# Tritag_Color_Sensor_Board_1_1.net
KiCad netlist of a schematic drawn in EAGLE
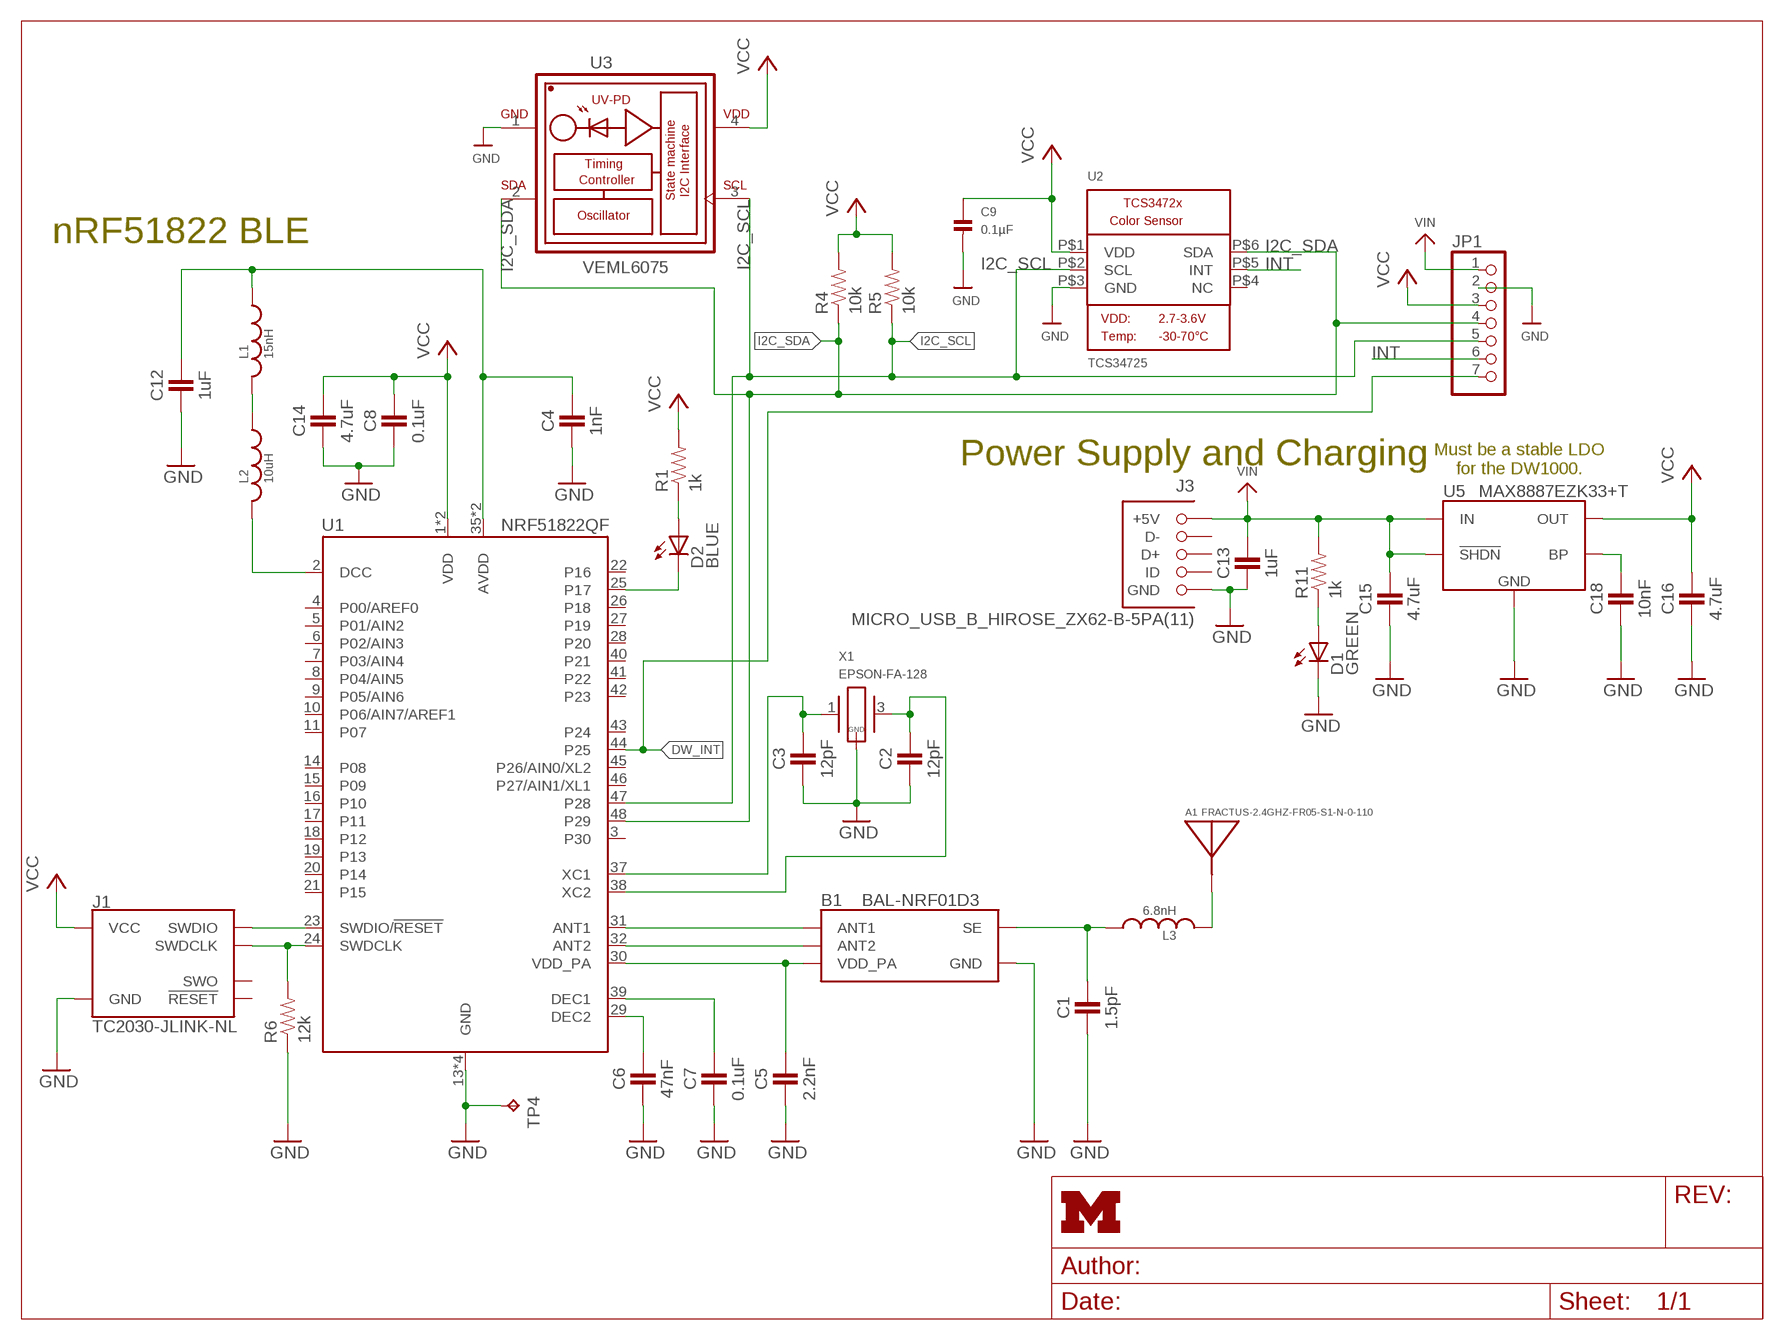
[diagram p0: schematic, sheet 1]

(export (version "E")
  (design (tool "Eeschema 10.0.6"))
  (components
    (comp (ref "A1")
      (value "FRACTUS-2.4GHZ-FR05-S1-N-0-110")
      (footprint "eagle-import:FRACTUS-ANTENNA-FR05-S1-N-0-110")
      (libsource (lib "eagle-import") (part "FRACTUS-2.4GHZ-FR05-S1-N-0-110"))
    )
    (comp (ref "B1")
      (value "BAL-NRF01D3")
      (footprint "eagle-import:BAL-NRF01D3")
      (libsource (lib "eagle-import") (part "BAL-NRF01D3"))
    )
    (comp (ref "C1")
      (value "1.5pF")
      (footprint "eagle-import:0402_CAP")
      (libsource (lib "eagle-import") (part "CAPACITOR"))
    )
    (comp (ref "C2")
      (value "12pF")
      (footprint "eagle-import:0402_CAP")
      (libsource (lib "eagle-import") (part "CAPACITOR"))
    )
    (comp (ref "C3")
      (value "12pF")
      (footprint "eagle-import:0402_CAP")
      (libsource (lib "eagle-import") (part "CAPACITOR"))
    )
    (comp (ref "C4")
      (value "1nF")
      (footprint "eagle-import:0402_CAP")
      (libsource (lib "eagle-import") (part "CAPACITOR"))
    )
    (comp (ref "C5")
      (value "2.2nF")
      (footprint "eagle-import:0402_CAP")
      (libsource (lib "eagle-import") (part "CAPACITOR"))
    )
    (comp (ref "C6")
      (value "47nF")
      (footprint "eagle-import:0402_CAP")
      (libsource (lib "eagle-import") (part "CAPACITOR"))
    )
    (comp (ref "C7")
      (value "0.1uF")
      (footprint "eagle-import:0402_CAP")
      (libsource (lib "eagle-import") (part "CAPACITOR"))
    )
    (comp (ref "C8")
      (value "0.1uF")
      (footprint "eagle-import:0402_CAP")
      (libsource (lib "eagle-import") (part "CAPACITOR"))
    )
    (comp (ref "C9")
      (value "0.1µF")
      (footprint "eagle-import:_0805")
      (libsource (lib "eagle-import") (part "CAP_CERAMIC_0805"))
    )
    (comp (ref "C12")
      (value "1uF")
      (footprint "eagle-import:0402_CAP")
      (libsource (lib "eagle-import") (part "CAPACITOR"))
    )
    (comp (ref "C13")
      (value "1uF")
      (footprint "eagle-import:0402_CAP")
      (libsource (lib "eagle-import") (part "CAPACITOR"))
    )
    (comp (ref "C14")
      (value "4.7uF")
      (footprint "eagle-import:0402_CAP")
      (libsource (lib "eagle-import") (part "CAPACITOR"))
    )
    (comp (ref "C15")
      (value "4.7uF")
      (footprint "eagle-import:0402_CAP")
      (libsource (lib "eagle-import") (part "CAPACITOR"))
    )
    (comp (ref "C16")
      (value "4.7uF")
      (footprint "eagle-import:0402_CAP")
      (libsource (lib "eagle-import") (part "CAPACITOR"))
    )
    (comp (ref "C18")
      (value "10nF")
      (footprint "eagle-import:0402_CAP")
      (libsource (lib "eagle-import") (part "CAPACITOR"))
    )
    (comp (ref "D1")
      (value "GREEN")
      (footprint "eagle-import:LED-0603")
      (libsource (lib "eagle-import") (part "LED0603"))
    )
    (comp (ref "D2")
      (value "BLUE")
      (footprint "eagle-import:LED-0603")
      (libsource (lib "eagle-import") (part "LED0603"))
    )
    (comp (ref "J1")
      (value "TC2030-JLINK-NL")
      (footprint "eagle-import:TC2030-IDC-NL")
      (libsource (lib "eagle-import") (part "TC2030-JLINK-NL"))
    )
    (comp (ref "J3")
      (value "MICRO_USB_B_HIROSE_ZX62-B-5PA(11)")
      (footprint "eagle-import:USB_MICRO_B-HIROSE-ZX62-B-5PA(11)")
      (libsource (lib "eagle-import") (part "MICRO_USB_B_HIROSE_ZX62-B-5PA(11)"))
    )
    (comp (ref "JP1")
      (value "HEADER-1X770MIL")
      (footprint "eagle-import:1X07_ROUND_70")
      (libsource (lib "eagle-import") (part "HEADER-1X770MIL"))
    )
    (comp (ref "L1")
      (value "15nH")
      (footprint "eagle-import:0402_CAP")
      (libsource (lib "eagle-import") (part "INDUCTOR0402"))
    )
    (comp (ref "L2")
      (value "10uH")
      (footprint "eagle-import:0603_CAP")
      (libsource (lib "eagle-import") (part "INDUCTOR0603"))
    )
    (comp (ref "L3")
      (value "6.8nH")
      (footprint "eagle-import:0402_CAP")
      (libsource (lib "eagle-import") (part "INDUCTOR0402"))
    )
    (comp (ref "R1")
      (value "1k")
      (footprint "eagle-import:0402_RES")
      (libsource (lib "eagle-import") (part "RESISTOR0402_RES"))
    )
    (comp (ref "R4")
      (value "10k")
      (footprint "eagle-import:0402_RES")
      (libsource (lib "eagle-import") (part "RESISTOR0402_RES"))
    )
    (comp (ref "R5")
      (value "10k")
      (footprint "eagle-import:0402_RES")
      (libsource (lib "eagle-import") (part "RESISTOR0402_RES"))
    )
    (comp (ref "R6")
      (value "12k")
      (footprint "eagle-import:0402_RES")
      (libsource (lib "eagle-import") (part "RESISTOR0402_RES"))
    )
    (comp (ref "R11")
      (value "1k")
      (footprint "eagle-import:0402_RES")
      (libsource (lib "eagle-import") (part "RESISTOR0402_RES"))
    )
    (comp (ref "TP4")
      (value "TPTP06SQ")
      (footprint "eagle-import:TP06SQ")
      (libsource (lib "eagle-import") (part "TPTP06SQ"))
    )
    (comp (ref "U1")
      (value "NRF51822QF")
      (footprint "eagle-import:QFN-48-6MM")
      (libsource (lib "eagle-import") (part "NRF51822QF"))
    )
    (comp (ref "U2")
      (value "TCS34725")
      (footprint "eagle-import:TCS3472_FN6")
      (libsource (lib "eagle-import") (part "LIGHT_TCS3472"))
    )
    (comp (ref "U3")
      (value "VEML6075")
      (footprint "eagle-import:VISHAY_VEML6075_1.25X2X1")
      (fields
        (field (name "DIGI-KEY_PART_NUMBER") "VEML6075CT-ND")
        (field (name "MF") "Vishay Semiconductor")
      )
      (libsource (lib "eagle-import") (part "VEML6075"))
    )
    (comp (ref "U5")
      (value "MAX8887EZK33+T")
      (footprint "eagle-import:SOT-23-5")
      (libsource (lib "eagle-import") (part "MAX8887EZK33+T"))
    )
    (comp (ref "X1")
      (value "EPSON-FA-128")
      (footprint "eagle-import:FA-128")
      (libsource (lib "eagle-import") (part "EPSON-FA-128"))
    )
  )
  (nets
    (net (code "1") (name "/INT") (class "Default")
      (node (ref "JP1") (pin "6") (pinfunction "6_6") (pintype "passive"))
      (node (ref "U2") (pin "P$5") (pinfunction "INT_P$5") (pintype "output"))
    )
    (net (code "2") (name "DW_INT") (class "Default")
      (node (ref "JP1") (pin "7") (pinfunction "7_7") (pintype "passive"))
      (node (ref "U1") (pin "44") (pinfunction "P25_44") (pintype "bidirectional"))
    )
    (net (code "3") (name "GND") (class "Default")
      (node (ref "B1") (pin "GND") (pinfunction "GND_GND") (pintype "bidirectional"))
      (node (ref "C1") (pin "2") (pinfunction "2_2") (pintype "bidirectional"))
      (node (ref "C12") (pin "2") (pinfunction "2_2") (pintype "bidirectional"))
      (node (ref "C13") (pin "2") (pinfunction "2_2") (pintype "bidirectional"))
      (node (ref "C14") (pin "2") (pinfunction "2_2") (pintype "bidirectional"))
      (node (ref "C15") (pin "2") (pinfunction "2_2") (pintype "bidirectional"))
      (node (ref "C16") (pin "2") (pinfunction "2_2") (pintype "bidirectional"))
      (node (ref "C18") (pin "2") (pinfunction "2_2") (pintype "bidirectional"))
      (node (ref "C2") (pin "2") (pinfunction "2_2") (pintype "bidirectional"))
      (node (ref "C3") (pin "2") (pinfunction "2_2") (pintype "bidirectional"))
      (node (ref "C4") (pin "2") (pinfunction "2_2") (pintype "bidirectional"))
      (node (ref "C5") (pin "2") (pinfunction "2_2") (pintype "bidirectional"))
      (node (ref "C6") (pin "2") (pinfunction "2_2") (pintype "bidirectional"))
      (node (ref "C7") (pin "2") (pinfunction "2_2") (pintype "bidirectional"))
      (node (ref "C8") (pin "2") (pinfunction "2_2") (pintype "bidirectional"))
      (node (ref "C9") (pin "2") (pinfunction "P$2_2") (pintype "passive"))
      (node (ref "D1") (pin "C") (pinfunction "C_C") (pintype "passive"))
      (node (ref "J1") (pin "5") (pinfunction "GND_5") (pintype "bidirectional"))
      (node (ref "J3") (pin "5") (pinfunction "GND_5") (pintype "bidirectional"))
      (node (ref "JP1") (pin "2") (pinfunction "2_2") (pintype "passive"))
      (node (ref "R6") (pin "1") (pinfunction "1_1") (pintype "passive"))
      (node (ref "TP4") (pin "TP") (pinfunction "TP_TP") (pintype "input"))
      (node (ref "U1") (pin "13") (pinfunction "GND_13") (pintype "bidirectional"))
      (node (ref "U1") (pin "33") (pinfunction "GND_33") (pintype "bidirectional"))
      (node (ref "U1") (pin "34") (pinfunction "GND_34") (pintype "bidirectional"))
      (node (ref "U1") (pin "GND") (pinfunction "GND_GND") (pintype "bidirectional"))
      (node (ref "U2") (pin "P$3") (pinfunction "GND_P$3") (pintype "power_in"))
      (node (ref "U3") (pin "1") (pinfunction "GND_1") (pintype "power_in"))
      (node (ref "U5") (pin "2") (pinfunction "GND_2") (pintype "bidirectional"))
      (node (ref "X1") (pin "2") (pinfunction "GND_2") (pintype "bidirectional"))
      (node (ref "X1") (pin "4") (pinfunction "GND_4") (pintype "bidirectional"))
    )
    (net (code "4") (name "I2C_SCL") (class "Default")
      (node (ref "JP1") (pin "5") (pinfunction "5_5") (pintype "passive"))
      (node (ref "R5") (pin "1") (pinfunction "1_1") (pintype "passive"))
      (node (ref "U1") (pin "47") (pinfunction "P28_47") (pintype "bidirectional"))
      (node (ref "U2") (pin "P$2") (pinfunction "SCL_P$2") (pintype "bidirectional"))
      (node (ref "U3") (pin "3") (pinfunction "SCL_3") (pintype "input"))
    )
    (net (code "5") (name "I2C_SDA") (class "Default")
      (node (ref "JP1") (pin "4") (pinfunction "4_4") (pintype "passive"))
      (node (ref "R4") (pin "1") (pinfunction "1_1") (pintype "passive"))
      (node (ref "U1") (pin "48") (pinfunction "P29_48") (pintype "bidirectional"))
      (node (ref "U2") (pin "P$6") (pinfunction "SDA_P$6") (pintype "bidirectional"))
      (node (ref "U3") (pin "2") (pinfunction "SDA_2") (pintype "bidirectional"))
    )
    (net (code "6") (name "Net-(A1-ANTENNA)") (class "Default")
      (node (ref "A1") (pin "ANT") (pinfunction "ANTENNA_ANT") (pintype "bidirectional"))
      (node (ref "L3") (pin "2") (pinfunction "2_2") (pintype "bidirectional"))
    )
    (net (code "7") (name "Net-(B1-PadSE)") (class "Default")
      (node (ref "B1") (pin "SE") (pinfunction "SE_SE") (pintype "bidirectional"))
      (node (ref "C1") (pin "1") (pinfunction "1_1") (pintype "bidirectional"))
      (node (ref "L3") (pin "1") (pinfunction "1_1") (pintype "bidirectional"))
    )
    (net (code "8") (name "Net-(B1-VDD_PA)") (class "Default")
      (node (ref "B1") (pin "VCC") (pinfunction "VDD_PA_VCC") (pintype "bidirectional"))
      (node (ref "C5") (pin "1") (pinfunction "1_1") (pintype "bidirectional"))
      (node (ref "U1") (pin "30") (pinfunction "VDD_PA_30") (pintype "bidirectional"))
    )
    (net (code "9") (name "Net-(C12-Pad1)") (class "Default")
      (node (ref "C12") (pin "1") (pinfunction "1_1") (pintype "bidirectional"))
      (node (ref "C4") (pin "1") (pinfunction "1_1") (pintype "bidirectional"))
      (node (ref "L1") (pin "1") (pinfunction "1_1") (pintype "bidirectional"))
      (node (ref "U1") (pin "35") (pinfunction "AVDD_35") (pintype "bidirectional"))
      (node (ref "U1") (pin "36") (pinfunction "AVDD_36") (pintype "bidirectional"))
    )
    (net (code "10") (name "Net-(D1-PadA)") (class "Default")
      (node (ref "D1") (pin "A") (pinfunction "A_A") (pintype "passive"))
      (node (ref "R11") (pin "1") (pinfunction "1_1") (pintype "passive"))
    )
    (net (code "11") (name "Net-(D2-PadA)") (class "Default")
      (node (ref "D2") (pin "A") (pinfunction "A_A") (pintype "passive"))
      (node (ref "R1") (pin "1") (pinfunction "1_1") (pintype "passive"))
    )
    (net (code "12") (name "Net-(J1-SWDCLK)") (class "Default")
      (node (ref "J1") (pin "4") (pinfunction "SWDCLK_4") (pintype "bidirectional"))
      (node (ref "R6") (pin "2") (pinfunction "2_2") (pintype "passive"))
      (node (ref "U1") (pin "24") (pinfunction "SWDCLK_24") (pintype "bidirectional"))
    )
    (net (code "13") (name "Net-(J1-SWDIO)") (class "Default")
      (node (ref "J1") (pin "2") (pinfunction "SWDIO_2") (pintype "bidirectional"))
      (node (ref "U1") (pin "23") (pinfunction "SWDIO/~{RESET}_23") (pintype "bidirectional"))
    )
    (net (code "14") (name "Net-(L1-Pad2)") (class "Default")
      (node (ref "L1") (pin "2") (pinfunction "2_2") (pintype "bidirectional"))
      (node (ref "L2") (pin "1") (pinfunction "1_1") (pintype "bidirectional"))
    )
    (net (code "15") (name "Net-(U1-ANT1)") (class "Default")
      (node (ref "B1") (pin "ANT1") (pinfunction "ANT1_ANT1") (pintype "bidirectional"))
      (node (ref "U1") (pin "31") (pinfunction "ANT1_31") (pintype "bidirectional"))
    )
    (net (code "16") (name "Net-(U1-ANT2)") (class "Default")
      (node (ref "B1") (pin "ANT2") (pinfunction "ANT2_ANT2") (pintype "bidirectional"))
      (node (ref "U1") (pin "32") (pinfunction "ANT2_32") (pintype "bidirectional"))
    )
    (net (code "17") (name "Net-(U1-DCC)") (class "Default")
      (node (ref "L2") (pin "2") (pinfunction "2_2") (pintype "bidirectional"))
      (node (ref "U1") (pin "2") (pinfunction "DCC_2") (pintype "bidirectional"))
    )
    (net (code "18") (name "Net-(U1-DEC1)") (class "Default")
      (node (ref "C7") (pin "1") (pinfunction "1_1") (pintype "bidirectional"))
      (node (ref "U1") (pin "39") (pinfunction "DEC1_39") (pintype "bidirectional"))
    )
    (net (code "19") (name "Net-(U1-DEC2)") (class "Default")
      (node (ref "C6") (pin "1") (pinfunction "1_1") (pintype "bidirectional"))
      (node (ref "U1") (pin "29") (pinfunction "DEC2_29") (pintype "bidirectional"))
    )
    (net (code "20") (name "Net-(U1-P17)") (class "Default")
      (node (ref "D2") (pin "C") (pinfunction "C_C") (pintype "passive"))
      (node (ref "U1") (pin "25") (pinfunction "P17_25") (pintype "bidirectional"))
    )
    (net (code "21") (name "Net-(U1-XC1)") (class "Default")
      (node (ref "C3") (pin "1") (pinfunction "1_1") (pintype "bidirectional"))
      (node (ref "U1") (pin "37") (pinfunction "XC1_37") (pintype "bidirectional"))
      (node (ref "X1") (pin "1") (pinfunction "1_1") (pintype "bidirectional"))
    )
    (net (code "22") (name "Net-(U1-XC2)") (class "Default")
      (node (ref "C2") (pin "1") (pinfunction "1_1") (pintype "bidirectional"))
      (node (ref "U1") (pin "38") (pinfunction "XC2_38") (pintype "bidirectional"))
      (node (ref "X1") (pin "3") (pinfunction "2_3") (pintype "bidirectional"))
    )
    (net (code "23") (name "Net-(U5-BP)") (class "Default")
      (node (ref "C18") (pin "1") (pinfunction "1_1") (pintype "bidirectional"))
      (node (ref "U5") (pin "4") (pinfunction "BP_4") (pintype "bidirectional"))
    )
    (net (code "24") (name "VCC") (class "Default")
      (node (ref "C14") (pin "1") (pinfunction "1_1") (pintype "bidirectional"))
      (node (ref "C16") (pin "1") (pinfunction "1_1") (pintype "bidirectional"))
      (node (ref "C8") (pin "1") (pinfunction "1_1") (pintype "bidirectional"))
      (node (ref "C9") (pin "1") (pinfunction "P$1_1") (pintype "passive"))
      (node (ref "J1") (pin "1") (pinfunction "VCC_1") (pintype "bidirectional"))
      (node (ref "JP1") (pin "3") (pinfunction "3_3") (pintype "passive"))
      (node (ref "R1") (pin "2") (pinfunction "2_2") (pintype "passive"))
      (node (ref "R4") (pin "2") (pinfunction "2_2") (pintype "passive"))
      (node (ref "R5") (pin "2") (pinfunction "2_2") (pintype "passive"))
      (node (ref "U1") (pin "1") (pinfunction "VDD_1") (pintype "bidirectional"))
      (node (ref "U1") (pin "12") (pinfunction "VDD_12") (pintype "bidirectional"))
      (node (ref "U2") (pin "P$1") (pinfunction "VDD_P$1") (pintype "power_in"))
      (node (ref "U3") (pin "4") (pinfunction "VDD_4") (pintype "power_in"))
      (node (ref "U5") (pin "5") (pinfunction "OUT_5") (pintype "bidirectional"))
    )
    (net (code "25") (name "VIN") (class "Default")
      (node (ref "C13") (pin "1") (pinfunction "1_1") (pintype "bidirectional"))
      (node (ref "C15") (pin "1") (pinfunction "1_1") (pintype "bidirectional"))
      (node (ref "J3") (pin "1") (pinfunction "+5V_1") (pintype "bidirectional"))
      (node (ref "JP1") (pin "1") (pinfunction "1_1") (pintype "passive"))
      (node (ref "R11") (pin "2") (pinfunction "2_2") (pintype "passive"))
      (node (ref "U5") (pin "1") (pinfunction "IN_1") (pintype "bidirectional"))
      (node (ref "U5") (pin "3") (pinfunction "~{SHDN}_3") (pintype "bidirectional"))
    )
    (net (code "26") (name "unconnected-(J1-SWO-Pad6)") (class "Default")
      (node (ref "J1") (pin "6") (pinfunction "SWO_6") (pintype "bidirectional"))
    )
    (net (code "27") (name "unconnected-(J1-~{RESET}-Pad3)") (class "Default")
      (node (ref "J1") (pin "3") (pinfunction "~{RESET}_3") (pintype "bidirectional"))
    )
    (net (code "28") (name "unconnected-(J3-D+-Pad3)") (class "Default")
      (node (ref "J3") (pin "3") (pinfunction "D+_3") (pintype "bidirectional"))
    )
    (net (code "29") (name "unconnected-(J3-D--Pad2)") (class "Default")
      (node (ref "J3") (pin "2") (pinfunction "D-_2") (pintype "bidirectional"))
    )
    (net (code "30") (name "unconnected-(J3-ID-Pad4)") (class "Default")
      (node (ref "J3") (pin "4") (pinfunction "ID_4") (pintype "bidirectional"))
    )
    (net (code "31") (name "unconnected-(U1-P00{slash}AREF0-Pad4)") (class "Default")
      (node (ref "U1") (pin "4") (pinfunction "P00/AREF0_4") (pintype "bidirectional"))
    )
    (net (code "32") (name "unconnected-(U1-P01{slash}AIN2-Pad5)") (class "Default")
      (node (ref "U1") (pin "5") (pinfunction "P01/AIN2_5") (pintype "bidirectional"))
    )
    (net (code "33") (name "unconnected-(U1-P02{slash}AIN3-Pad6)") (class "Default")
      (node (ref "U1") (pin "6") (pinfunction "P02/AIN3_6") (pintype "bidirectional"))
    )
    (net (code "34") (name "unconnected-(U1-P03{slash}AIN4-Pad7)") (class "Default")
      (node (ref "U1") (pin "7") (pinfunction "P03/AIN4_7") (pintype "bidirectional"))
    )
    (net (code "35") (name "unconnected-(U1-P04{slash}AIN5-Pad8)") (class "Default")
      (node (ref "U1") (pin "8") (pinfunction "P04/AIN5_8") (pintype "bidirectional"))
    )
    (net (code "36") (name "unconnected-(U1-P05{slash}AIN6-Pad9)") (class "Default")
      (node (ref "U1") (pin "9") (pinfunction "P05/AIN6_9") (pintype "bidirectional"))
    )
    (net (code "37") (name "unconnected-(U1-P06{slash}AIN7{slash}AREF1-Pad10)") (class "Default")
      (node (ref "U1") (pin "10") (pinfunction "P06/AIN7/AREF1_10") (pintype "bidirectional"))
    )
    (net (code "38") (name "unconnected-(U1-P07-Pad11)") (class "Default")
      (node (ref "U1") (pin "11") (pinfunction "P07_11") (pintype "bidirectional"))
    )
    (net (code "39") (name "unconnected-(U1-P08-Pad14)") (class "Default")
      (node (ref "U1") (pin "14") (pinfunction "P08_14") (pintype "bidirectional"))
    )
    (net (code "40") (name "unconnected-(U1-P09-Pad15)") (class "Default")
      (node (ref "U1") (pin "15") (pinfunction "P09_15") (pintype "bidirectional"))
    )
    (net (code "41") (name "unconnected-(U1-P10-Pad16)") (class "Default")
      (node (ref "U1") (pin "16") (pinfunction "P10_16") (pintype "bidirectional"))
    )
    (net (code "42") (name "unconnected-(U1-P11-Pad17)") (class "Default")
      (node (ref "U1") (pin "17") (pinfunction "P11_17") (pintype "bidirectional"))
    )
    (net (code "43") (name "unconnected-(U1-P12-Pad18)") (class "Default")
      (node (ref "U1") (pin "18") (pinfunction "P12_18") (pintype "bidirectional"))
    )
    (net (code "44") (name "unconnected-(U1-P13-Pad19)") (class "Default")
      (node (ref "U1") (pin "19") (pinfunction "P13_19") (pintype "bidirectional"))
    )
    (net (code "45") (name "unconnected-(U1-P14-Pad20)") (class "Default")
      (node (ref "U1") (pin "20") (pinfunction "P14_20") (pintype "bidirectional"))
    )
    (net (code "46") (name "unconnected-(U1-P15-Pad21)") (class "Default")
      (node (ref "U1") (pin "21") (pinfunction "P15_21") (pintype "bidirectional"))
    )
    (net (code "47") (name "unconnected-(U1-P16-Pad22)") (class "Default")
      (node (ref "U1") (pin "22") (pinfunction "P16_22") (pintype "bidirectional"))
    )
    (net (code "48") (name "unconnected-(U1-P18-Pad26)") (class "Default")
      (node (ref "U1") (pin "26") (pinfunction "P18_26") (pintype "bidirectional"))
    )
    (net (code "49") (name "unconnected-(U1-P19-Pad27)") (class "Default")
      (node (ref "U1") (pin "27") (pinfunction "P19_27") (pintype "bidirectional"))
    )
    (net (code "50") (name "unconnected-(U1-P20-Pad28)") (class "Default")
      (node (ref "U1") (pin "28") (pinfunction "P20_28") (pintype "bidirectional"))
    )
    (net (code "51") (name "unconnected-(U1-P21-Pad40)") (class "Default")
      (node (ref "U1") (pin "40") (pinfunction "P21_40") (pintype "bidirectional"))
    )
    (net (code "52") (name "unconnected-(U1-P22-Pad41)") (class "Default")
      (node (ref "U1") (pin "41") (pinfunction "P22_41") (pintype "bidirectional"))
    )
    (net (code "53") (name "unconnected-(U1-P23-Pad42)") (class "Default")
      (node (ref "U1") (pin "42") (pinfunction "P23_42") (pintype "bidirectional"))
    )
    (net (code "54") (name "unconnected-(U1-P24-Pad43)") (class "Default")
      (node (ref "U1") (pin "43") (pinfunction "P24_43") (pintype "bidirectional"))
    )
    (net (code "55") (name "unconnected-(U1-P26{slash}AIN0{slash}XL2-Pad45)") (class "Default")
      (node (ref "U1") (pin "45") (pinfunction "P26/AIN0/XL2_45") (pintype "bidirectional"))
    )
    (net (code "56") (name "unconnected-(U1-P27{slash}AIN1{slash}XL1-Pad46)") (class "Default")
      (node (ref "U1") (pin "46") (pinfunction "P27/AIN1/XL1_46") (pintype "bidirectional"))
    )
    (net (code "57") (name "unconnected-(U1-P30-Pad3)") (class "Default")
      (node (ref "U1") (pin "3") (pinfunction "P30_3") (pintype "bidirectional"))
    )
    (net (code "58") (name "unconnected-(U2-NC-PadP$4)") (class "Default")
      (node (ref "U2") (pin "P$4") (pinfunction "NC_P$4") (pintype "no_connect"))
    )
  )
)
